# Jetson_CAN.net
KiCad netlist of a schematic drawn in Altium Designer
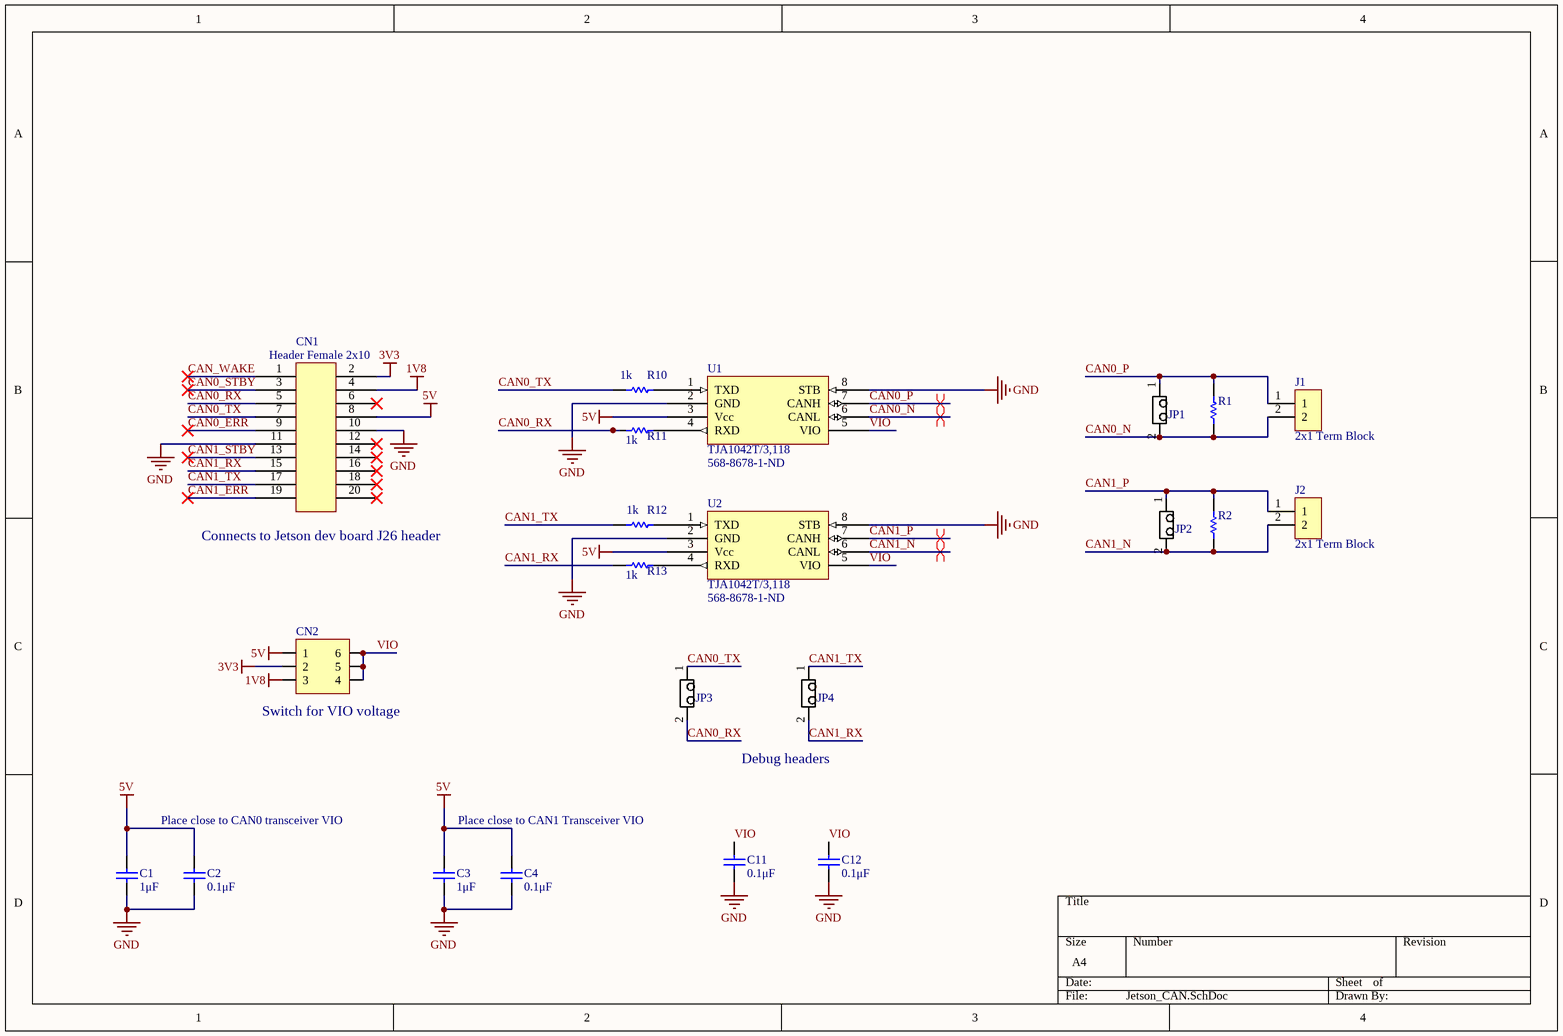
[diagram p0: Jetson_CAN.SchDoc]

(export (version "E")
  (design (tool "Eeschema 10.0.6"))
  (components
    (comp (ref "C1")
      (value "1μF")
      (footprint "CAPC1608N(0603\")")
      (description "Capacitor, Ceramic, 50V, +/- 10%, 0603 SMD, X5R")
      (fields (field (name "CREATED BY") "Lyden Smith"))
      (libsource (lib "AUVic_Integrated_Library_Capacitors") (part "1uF 50V 0603 SMD, Ceramic"))
    )
    (comp (ref "C2")
      (value "0.1μF")
      (footprint "CAPC1608N(0603\")")
      (description "Capacitor, Ceramic, 16V, +/- 10%, 0603 SMD, X7R")
      (fields (field (name "PUBLISHER") "AUVic") (field (name "CREATED BY") "Andy Bates"))
      (libsource (lib "AUVic_Integrated_Library_Capacitors") (part "0.1uF 16V 0603 SMD, Ceramic"))
    )
    (comp (ref "C3")
      (value "1μF")
      (footprint "CAPC1608N(0603\")")
      (description "Capacitor, Ceramic, 50V, +/- 10%, 0603 SMD, X5R")
      (fields (field (name "CREATED BY") "Lyden Smith"))
      (libsource (lib "AUVic_Integrated_Library_Capacitors") (part "1uF 50V 0603 SMD, Ceramic"))
    )
    (comp (ref "C4")
      (value "0.1μF")
      (footprint "CAPC1608N(0603\")")
      (description "Capacitor, Ceramic, 16V, +/- 10%, 0603 SMD, X7R")
      (fields (field (name "PUBLISHER") "AUVic") (field (name "CREATED BY") "Andy Bates"))
      (libsource (lib "AUVic_Integrated_Library_Capacitors") (part "0.1uF 16V 0603 SMD, Ceramic"))
    )
    (comp (ref "C11")
      (value "0.1μF")
      (footprint "CAPC1608N(0603\")")
      (description "Capacitor, Ceramic, 16V, +/- 10%, 0603 SMD, X7R")
      (fields (field (name "PUBLISHER") "AUVic") (field (name "CREATED BY") "Andy Bates"))
      (libsource (lib "AUVic_Integrated_Library_Capacitors") (part "0.1uF 16V 0603 SMD, Ceramic"))
    )
    (comp (ref "C12")
      (value "0.1μF")
      (footprint "CAPC1608N(0603\")")
      (description "Capacitor, Ceramic, 16V, +/- 10%, 0603 SMD, X7R")
      (fields (field (name "PUBLISHER") "AUVic") (field (name "CREATED BY") "Andy Bates"))
      (libsource (lib "AUVic_Integrated_Library_Capacitors") (part "0.1uF 16V 0603 SMD, Ceramic"))
    )
    (comp (ref "CN1")
      (value "Header Female 2x10")
      (footprint "HEADER, FEMALE/MALE, 2x10, 100mil")
      (description "Header, Female with extended Male pins, 2x10, THT, 100mil")
      (fields (field (name "CREATED BY") "Poorna Chander Kalidas"))
      (libsource (lib "AUVic_Integrated_Library_Connectors") (part "Header, Female/Male, 2x10, THT, 100mil"))
    )
    (comp (ref "CN2")
      (value "Header, Male, 2x3, Pitch: 0.1\" (2.54mm), THT")
      (footprint "Header, Male, 2x3, Pitch: 0.1\" (2.54mm),THT")
      (fields
        (field (name "PUBLISHER") "AUVic")
        (field (name "REVIEWED BY") "*")
        (field (name "CREATED BY") "Andy Bates")
      )
      (libsource (lib "AUVic_Integrated_Library_Connectors") (part "Header, Male, 2x3, Pitch{colon} 0.1{dblquote} (2.54mm), THT"))
    )
    (comp (ref "J1")
      (value "2x1 Term Block")
      (footprint "2X1 Terminal Blocks")
      (fields (field (name "MADE BY") "Andy Bates"))
      (libsource (lib "AUVic_Integrated_Library_Connectors") (part "2x1 Terminal Block"))
    )
    (comp (ref "J2")
      (value "2x1 Term Block")
      (footprint "2X1 Terminal Blocks")
      (fields (field (name "MADE BY") "Andy Bates"))
      (libsource (lib "AUVic_Integrated_Library_Connectors") (part "2x1 Terminal Block"))
    )
    (comp (ref "JP1")
      (value "1X2 Pin Head")
      (footprint "2X1 Males Header")
      (fields (field (name "MADE BY") "Andy Bates"))
      (libsource (lib "AUVic_Integrated_Library_Connectors") (part "1x2 Male Header"))
    )
    (comp (ref "JP2")
      (value "1X2 Pin Head")
      (footprint "2X1 Males Header")
      (fields (field (name "MADE BY") "Andy Bates"))
      (libsource (lib "AUVic_Integrated_Library_Connectors") (part "1x2 Male Header"))
    )
    (comp (ref "JP3")
      (value "1X2 Pin Head")
      (footprint "2X1 Males Header")
      (fields (field (name "MADE BY") "Andy Bates"))
      (libsource (lib "AUVic_Integrated_Library_Connectors") (part "1x2 Male Header"))
    )
    (comp (ref "JP4")
      (value "1X2 Pin Head")
      (footprint "2X1 Males Header")
      (fields (field (name "MADE BY") "Andy Bates"))
      (libsource (lib "AUVic_Integrated_Library_Connectors") (part "1x2 Male Header"))
    )
    (comp (ref "R1")
      (value "CRCW0603120KFKEA")
      (footprint "RESC1609X50X30NL10T20")
      (fields (field (name "MANUFACTURER") "Vishay Dale"))
      (libsource (lib "Altium Content Vault") (part "RES"))
    )
    (comp (ref "R2")
      (value "CRCW0603120KFKEA")
      (footprint "RESC1609X50X30NL10T20")
      (fields (field (name "MANUFACTURER") "Vishay Dale"))
      (libsource (lib "Altium Content Vault") (part "RES"))
    )
    (comp (ref "R10")
      (value "1k")
      (footprint "RESC1608N(0603\")")
      (description "1kR, 1%, 1/10W , 0603, SMD")
      (fields (field (name "CREATED BY") "Andy Bates") (field (name "PUBLISHER") "AUVic"))
      (libsource (lib "AUVic_Integrated_Library_Resistors") (part "1kR, 1%, 1/10W , 0603, SMD"))
    )
    (comp (ref "R11")
      (value "1k")
      (footprint "RESC1608N(0603\")")
      (description "1kR, 1%, 1/10W , 0603, SMD")
      (fields (field (name "CREATED BY") "Andy Bates") (field (name "PUBLISHER") "AUVic"))
      (libsource (lib "AUVic_Integrated_Library_Resistors") (part "1kR, 1%, 1/10W , 0603, SMD"))
    )
    (comp (ref "R12")
      (value "1k")
      (footprint "RESC1608N(0603\")")
      (description "1kR, 1%, 1/10W , 0603, SMD")
      (fields (field (name "CREATED BY") "Andy Bates") (field (name "PUBLISHER") "AUVic"))
      (libsource (lib "AUVic_Integrated_Library_Resistors") (part "1kR, 1%, 1/10W , 0603, SMD"))
    )
    (comp (ref "R13")
      (value "1k")
      (footprint "RESC1608N(0603\")")
      (description "1kR, 1%, 1/10W , 0603, SMD")
      (fields (field (name "CREATED BY") "Andy Bates") (field (name "PUBLISHER") "AUVic"))
      (libsource (lib "AUVic_Integrated_Library_Resistors") (part "1kR, 1%, 1/10W , 0603, SMD"))
    )
    (comp (ref "U1")
      (value "TJA1042T/3,118")
      (footprint "8-SOIC")
      (description "1/1 Transceiver Half CANbus 8-SO")
      (fields
        (field (name "SUPPLIER PART NUMBER 1") "568-8678-1-ND")
        (field (name "MADE BY") "Poorna Chander Kalidas")
      )
      (libsource (lib "AUVic_Integrated_Library_Interface") (part "CAN Transceiver"))
    )
    (comp (ref "U2")
      (value "TJA1042T/3,118")
      (footprint "8-SOIC")
      (description "1/1 Transceiver Half CANbus 8-SO")
      (fields
        (field (name "SUPPLIER PART NUMBER 1") "568-8678-1-ND")
        (field (name "MADE BY") "Poorna Chander Kalidas")
      )
      (libsource (lib "AUVic_Integrated_Library_Interface") (part "CAN Transceiver"))
    )
  )
  (nets
    (net (code "1") (name "/CAN0_ERR") (class "Default")
      (node (ref "CN1") (pin "9") (pintype "passive+no_connect"))
    )
    (net (code "2") (name "/CAN0_N") (class "Default")
      (node (ref "J1") (pin "2") (pinfunction "2_2") (pintype "passive"))
      (node (ref "JP1") (pin "2") (pinfunction "2_2") (pintype "passive"))
      (node (ref "R1") (pin "2") (pinfunction "2_2") (pintype "passive"))
      (node (ref "U1") (pin "6") (pinfunction "CANL_6") (pintype "bidirectional"))
    )
    (net (code "3") (name "/CAN0_P") (class "Default")
      (node (ref "J1") (pin "1") (pinfunction "1_1") (pintype "passive"))
      (node (ref "JP1") (pin "1") (pinfunction "1_1") (pintype "passive"))
      (node (ref "R1") (pin "1") (pinfunction "1_1") (pintype "passive"))
      (node (ref "U1") (pin "7") (pinfunction "CANH_7") (pintype "bidirectional"))
    )
    (net (code "4") (name "/CAN0_RX") (class "Default")
      (node (ref "CN1") (pin "5") (pintype "passive"))
      (node (ref "JP3") (pin "2") (pinfunction "2_2") (pintype "passive"))
      (node (ref "R11") (pin "1") (pinfunction "1_1") (pintype "passive"))
    )
    (net (code "5") (name "/CAN0_STBY") (class "Default")
      (node (ref "CN1") (pin "3") (pintype "passive+no_connect"))
    )
    (net (code "6") (name "/CAN0_TX") (class "Default")
      (node (ref "CN1") (pin "7") (pintype "passive"))
      (node (ref "JP3") (pin "1") (pinfunction "1_1") (pintype "passive"))
      (node (ref "R10") (pin "1") (pinfunction "1_1") (pintype "passive"))
    )
    (net (code "7") (name "/CAN1_ERR") (class "Default")
      (node (ref "CN1") (pin "19") (pintype "passive+no_connect"))
    )
    (net (code "8") (name "/CAN1_N") (class "Default")
      (node (ref "J2") (pin "2") (pinfunction "2_2") (pintype "passive"))
      (node (ref "JP2") (pin "2") (pinfunction "2_2") (pintype "passive"))
      (node (ref "R2") (pin "2") (pinfunction "2_2") (pintype "passive"))
      (node (ref "U2") (pin "6") (pinfunction "CANL_6") (pintype "bidirectional"))
    )
    (net (code "9") (name "/CAN1_P") (class "Default")
      (node (ref "J2") (pin "1") (pinfunction "1_1") (pintype "passive"))
      (node (ref "JP2") (pin "1") (pinfunction "1_1") (pintype "passive"))
      (node (ref "R2") (pin "1") (pinfunction "1_1") (pintype "passive"))
      (node (ref "U2") (pin "7") (pinfunction "CANH_7") (pintype "bidirectional"))
    )
    (net (code "10") (name "/CAN1_RX") (class "Default")
      (node (ref "CN1") (pin "15") (pintype "passive"))
      (node (ref "JP4") (pin "2") (pinfunction "2_2") (pintype "passive"))
      (node (ref "R13") (pin "1") (pinfunction "1_1") (pintype "passive"))
    )
    (net (code "11") (name "/CAN1_STBY") (class "Default")
      (node (ref "CN1") (pin "13") (pintype "passive+no_connect"))
    )
    (net (code "12") (name "/CAN1_TX") (class "Default")
      (node (ref "CN1") (pin "17") (pintype "passive"))
      (node (ref "JP4") (pin "1") (pinfunction "1_1") (pintype "passive"))
      (node (ref "R12") (pin "1") (pinfunction "1_1") (pintype "passive"))
    )
    (net (code "13") (name "/CAN_WAKE") (class "Default")
      (node (ref "CN1") (pin "1") (pintype "passive+no_connect"))
    )
    (net (code "14") (name "/VIO") (class "Default")
      (node (ref "C11") (pin "2") (pinfunction "Cathode_2") (pintype "passive"))
      (node (ref "C12") (pin "2") (pinfunction "Cathode_2") (pintype "passive"))
      (node (ref "CN2") (pin "4") (pinfunction "4_4") (pintype "passive"))
      (node (ref "CN2") (pin "5") (pinfunction "5_5") (pintype "passive"))
      (node (ref "CN2") (pin "6") (pinfunction "6_6") (pintype "passive"))
      (node (ref "U1") (pin "5") (pinfunction "VIO_5") (pintype "passive"))
      (node (ref "U2") (pin "5") (pinfunction "VIO_5") (pintype "passive"))
    )
    (net (code "15") (name "1V8") (class "Default")
      (node (ref "CN1") (pin "4") (pintype "passive"))
      (node (ref "CN2") (pin "3") (pinfunction "3_3") (pintype "passive"))
    )
    (net (code "16") (name "3V3") (class "Default")
      (node (ref "CN1") (pin "2") (pintype "passive"))
      (node (ref "CN2") (pin "2") (pinfunction "2_2") (pintype "passive"))
    )
    (net (code "17") (name "5V") (class "Default")
      (node (ref "C1") (pin "2") (pinfunction "Cathode_2") (pintype "passive"))
      (node (ref "C2") (pin "2") (pinfunction "Cathode_2") (pintype "passive"))
      (node (ref "C3") (pin "2") (pinfunction "Cathode_2") (pintype "passive"))
      (node (ref "C4") (pin "2") (pinfunction "Cathode_2") (pintype "passive"))
      (node (ref "CN1") (pin "8") (pintype "passive"))
      (node (ref "CN2") (pin "1") (pinfunction "1_1") (pintype "passive"))
      (node (ref "U1") (pin "3") (pinfunction "Vcc_3") (pintype "power_in"))
      (node (ref "U2") (pin "3") (pinfunction "Vcc_3") (pintype "power_in"))
    )
    (net (code "18") (name "GND") (class "Default")
      (node (ref "C1") (pin "1") (pinfunction "Anode_1") (pintype "passive"))
      (node (ref "C11") (pin "1") (pinfunction "Anode_1") (pintype "passive"))
      (node (ref "C12") (pin "1") (pinfunction "Anode_1") (pintype "passive"))
      (node (ref "C2") (pin "1") (pinfunction "Anode_1") (pintype "passive"))
      (node (ref "C3") (pin "1") (pinfunction "Anode_1") (pintype "passive"))
      (node (ref "C4") (pin "1") (pinfunction "Anode_1") (pintype "passive"))
      (node (ref "CN1") (pin "10") (pintype "passive"))
      (node (ref "CN1") (pin "11") (pintype "passive"))
      (node (ref "U1") (pin "2") (pinfunction "GND_2") (pintype "power_in"))
      (node (ref "U1") (pin "8") (pinfunction "STB_8") (pintype "input"))
      (node (ref "U2") (pin "2") (pinfunction "GND_2") (pintype "power_in"))
      (node (ref "U2") (pin "8") (pinfunction "STB_8") (pintype "input"))
    )
    (net (code "19") (name "Net-(U1-RXD)") (class "Default")
      (node (ref "R11") (pin "2") (pinfunction "2_2") (pintype "passive"))
      (node (ref "U1") (pin "4") (pinfunction "RXD_4") (pintype "output"))
    )
    (net (code "20") (name "Net-(U1-TXD)") (class "Default")
      (node (ref "R10") (pin "2") (pinfunction "2_2") (pintype "passive"))
      (node (ref "U1") (pin "1") (pinfunction "TXD_1") (pintype "input"))
    )
    (net (code "21") (name "Net-(U2-RXD)") (class "Default")
      (node (ref "R13") (pin "2") (pinfunction "2_2") (pintype "passive"))
      (node (ref "U2") (pin "4") (pinfunction "RXD_4") (pintype "output"))
    )
    (net (code "22") (name "Net-(U2-TXD)") (class "Default")
      (node (ref "R12") (pin "2") (pinfunction "2_2") (pintype "passive"))
      (node (ref "U2") (pin "1") (pinfunction "TXD_1") (pintype "input"))
    )
    (net (code "23") (name "unconnected-(CN1-Pad6)") (class "Default")
      (node (ref "CN1") (pin "6") (pintype "passive+no_connect"))
    )
    (net (code "24") (name "unconnected-(CN1-Pad12)") (class "Default")
      (node (ref "CN1") (pin "12") (pintype "passive+no_connect"))
    )
    (net (code "25") (name "unconnected-(CN1-Pad14)") (class "Default")
      (node (ref "CN1") (pin "14") (pintype "passive+no_connect"))
    )
    (net (code "26") (name "unconnected-(CN1-Pad16)") (class "Default")
      (node (ref "CN1") (pin "16") (pintype "passive+no_connect"))
    )
    (net (code "27") (name "unconnected-(CN1-Pad18)") (class "Default")
      (node (ref "CN1") (pin "18") (pintype "passive+no_connect"))
    )
    (net (code "28") (name "unconnected-(CN1-Pad20)") (class "Default")
      (node (ref "CN1") (pin "20") (pintype "passive+no_connect"))
    )
  )
)
